# radar.net
KiCad netlist of a schematic drawn in EAGLE
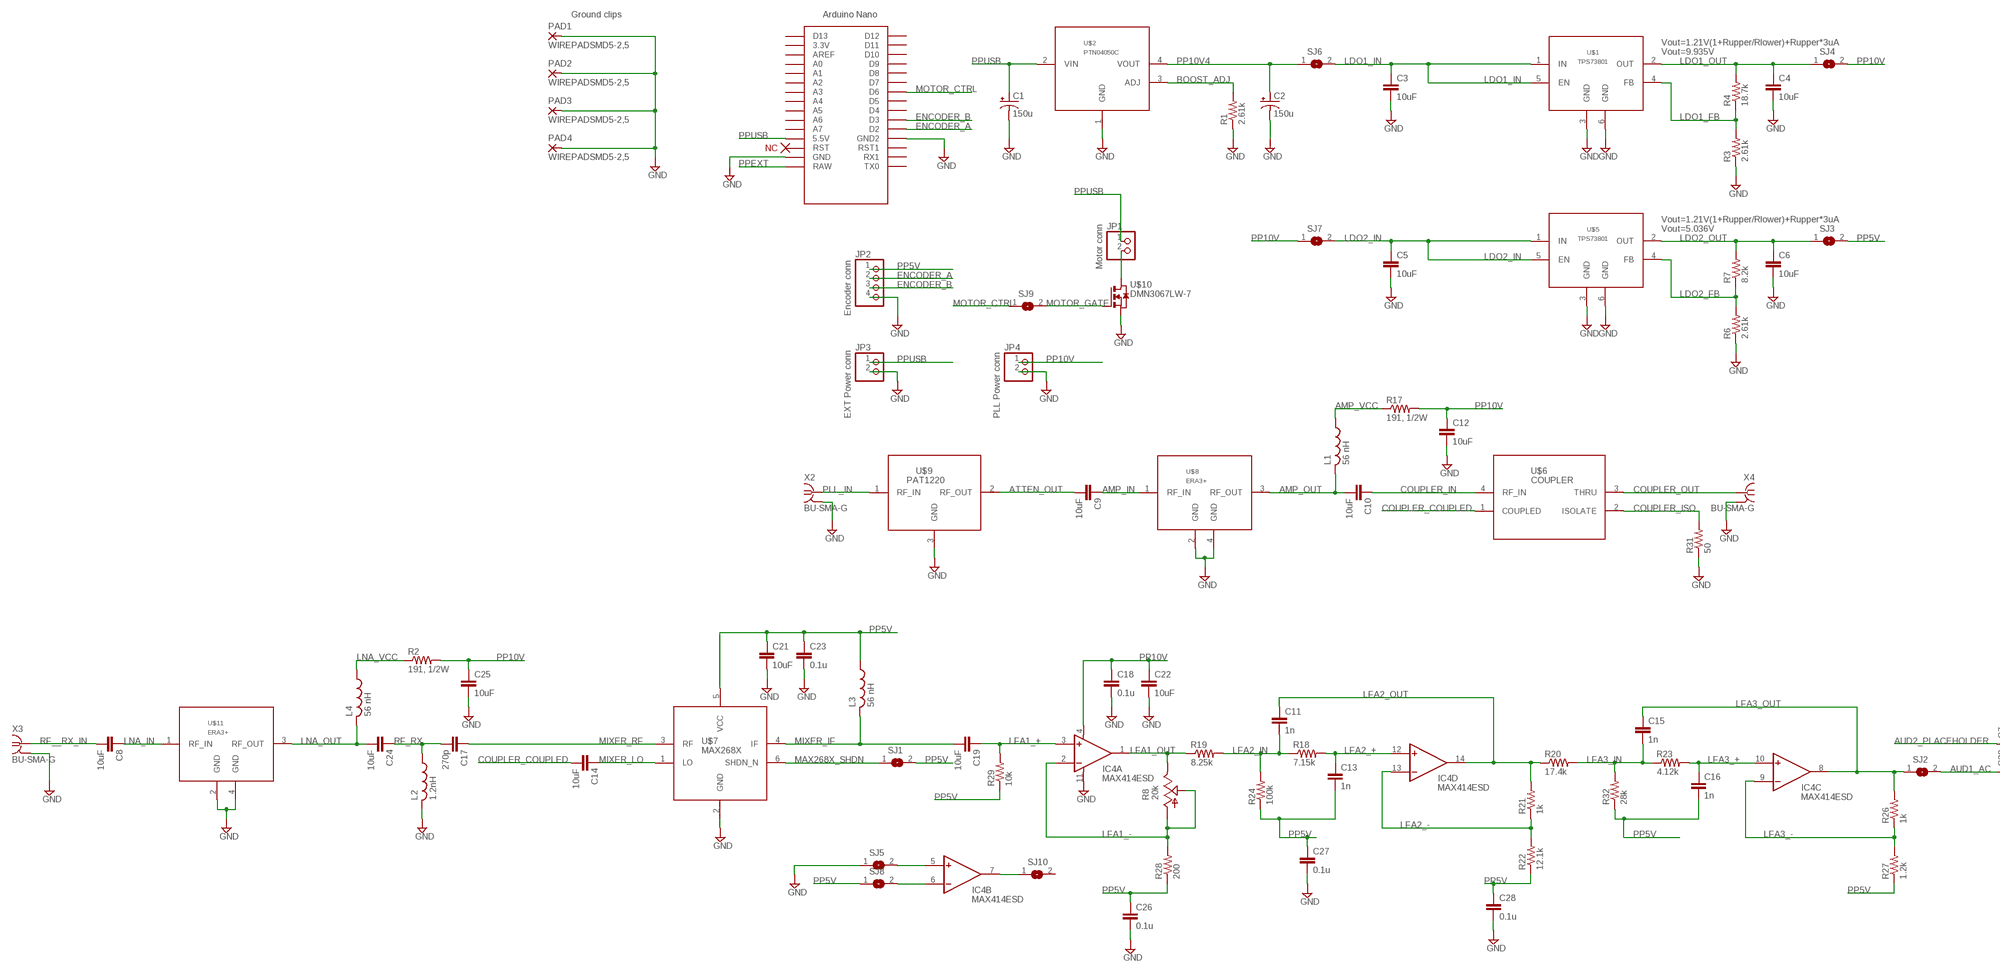
[diagram p0: schematic, sheet 1, part 1 of 2]
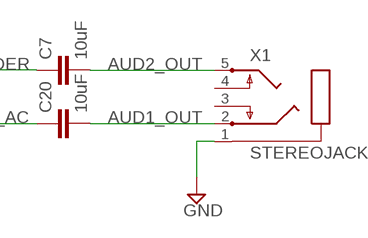
[diagram p1: schematic, sheet 1, part 2 of 2]

(export (version "E")
  (design (tool "Eeschema 10.0.6"))
  (components
    (comp (ref "C1")
      (value "150u")
      (footprint "eagle-import:153CLV-0605")
      (libsource (lib "eagle-import") (part "CPOL-US153CLV-0605"))
    )
    (comp (ref "C2")
      (value "150u")
      (footprint "eagle-import:153CLV-0605")
      (libsource (lib "eagle-import") (part "CPOL-US153CLV-0605"))
    )
    (comp (ref "C3")
      (value "10uF")
      (footprint "eagle-import:C0805K")
      (libsource (lib "eagle-import") (part "C-EUC0805K"))
    )
    (comp (ref "C4")
      (value "10uF")
      (footprint "eagle-import:C0805K")
      (libsource (lib "eagle-import") (part "C-EUC0805K"))
    )
    (comp (ref "C5")
      (value "10uF")
      (footprint "eagle-import:C0805K")
      (libsource (lib "eagle-import") (part "C-EUC0805K"))
    )
    (comp (ref "C6")
      (value "10uF")
      (footprint "eagle-import:C0805K")
      (libsource (lib "eagle-import") (part "C-EUC0805K"))
    )
    (comp (ref "C7")
      (value "10uF")
      (footprint "eagle-import:C0805K")
      (libsource (lib "eagle-import") (part "C-EUC0805K"))
    )
    (comp (ref "C8")
      (value "10uF")
      (footprint "eagle-import:C0805K")
      (libsource (lib "eagle-import") (part "C-EUC0805K"))
    )
    (comp (ref "C9")
      (value "10uF")
      (footprint "eagle-import:C0805K")
      (libsource (lib "eagle-import") (part "C-EUC0805K"))
    )
    (comp (ref "C10")
      (value "10uF")
      (footprint "eagle-import:C0805K")
      (libsource (lib "eagle-import") (part "C-EUC0805K"))
    )
    (comp (ref "C11")
      (value "1n")
      (footprint "eagle-import:C0603")
      (libsource (lib "eagle-import") (part "C-EUC0603"))
    )
    (comp (ref "C12")
      (value "10uF")
      (footprint "eagle-import:C0805K")
      (libsource (lib "eagle-import") (part "C-EUC0805K"))
    )
    (comp (ref "C13")
      (value "1n")
      (footprint "eagle-import:C0603")
      (libsource (lib "eagle-import") (part "C-EUC0603"))
    )
    (comp (ref "C14")
      (value "10uF")
      (footprint "eagle-import:C0805K")
      (libsource (lib "eagle-import") (part "C-EUC0805K"))
    )
    (comp (ref "C15")
      (value "1n")
      (footprint "eagle-import:C0603")
      (libsource (lib "eagle-import") (part "C-EUC0603"))
    )
    (comp (ref "C16")
      (value "1n")
      (footprint "eagle-import:C0603")
      (libsource (lib "eagle-import") (part "C-EUC0603"))
    )
    (comp (ref "C17")
      (value "270p")
      (footprint "eagle-import:C0603K")
      (libsource (lib "eagle-import") (part "C-EUC0603K"))
    )
    (comp (ref "C18")
      (value "0.1u")
      (footprint "eagle-import:C0603")
      (libsource (lib "eagle-import") (part "C-EUC0603"))
    )
    (comp (ref "C19")
      (value "10uF")
      (footprint "eagle-import:C0805K")
      (libsource (lib "eagle-import") (part "C-EUC0805K"))
    )
    (comp (ref "C20")
      (value "10uF")
      (footprint "eagle-import:C0805K")
      (libsource (lib "eagle-import") (part "C-EUC0805K"))
    )
    (comp (ref "C21")
      (value "10uF")
      (footprint "eagle-import:C0805K")
      (libsource (lib "eagle-import") (part "C-EUC0805K"))
    )
    (comp (ref "C22")
      (value "10uF")
      (footprint "eagle-import:C0805K")
      (libsource (lib "eagle-import") (part "C-EUC0805K"))
    )
    (comp (ref "C23")
      (value "0.1u")
      (footprint "eagle-import:C0603")
      (libsource (lib "eagle-import") (part "C-EUC0603"))
    )
    (comp (ref "C24")
      (value "10uF")
      (footprint "eagle-import:C0805K")
      (libsource (lib "eagle-import") (part "C-EUC0805K"))
    )
    (comp (ref "C25")
      (value "10uF")
      (footprint "eagle-import:C0805K")
      (libsource (lib "eagle-import") (part "C-EUC0805K"))
    )
    (comp (ref "C26")
      (value "0.1u")
      (footprint "eagle-import:C0603")
      (libsource (lib "eagle-import") (part "C-EUC0603"))
    )
    (comp (ref "C27")
      (value "0.1u")
      (footprint "eagle-import:C0603")
      (libsource (lib "eagle-import") (part "C-EUC0603"))
    )
    (comp (ref "C28")
      (value "0.1u")
      (footprint "eagle-import:C0603")
      (libsource (lib "eagle-import") (part "C-EUC0603"))
    )
    (comp (ref "IC4")
      (value "MAX414ESD")
      (footprint "eagle-import:SO14")
      (fields (field (name "DIGI") "MAX414ESD+-ND"))
      (libsource (lib "eagle-import") (part "MAX414ESD"))
    )
    (comp (ref "JP1")
      (value "PINHD-1X2")
      (footprint "eagle-import:1X02")
      (libsource (lib "eagle-import") (part "PINHD-1X2"))
    )
    (comp (ref "JP2")
      (value "PINHD-1X4")
      (footprint "eagle-import:1X04")
      (libsource (lib "eagle-import") (part "PINHD-1X4"))
    )
    (comp (ref "JP3")
      (value "PINHD-1X2")
      (footprint "eagle-import:1X02")
      (libsource (lib "eagle-import") (part "PINHD-1X2"))
    )
    (comp (ref "JP4")
      (value "PINHD-1X2")
      (footprint "eagle-import:1X02")
      (libsource (lib "eagle-import") (part "PINHD-1X2"))
    )
    (comp (ref "L1")
      (value "56 nH")
      (footprint "eagle-import:0603")
      (libsource (lib "eagle-import") (part "L0603"))
    )
    (comp (ref "L2")
      (value "1.2nH")
      (footprint "eagle-import:0603")
      (libsource (lib "eagle-import") (part "L0603"))
    )
    (comp (ref "L3")
      (value "56 nH")
      (footprint "eagle-import:0603")
      (libsource (lib "eagle-import") (part "L0603"))
    )
    (comp (ref "L4")
      (value "56 nH")
      (footprint "eagle-import:0603")
      (libsource (lib "eagle-import") (part "L0603"))
    )
    (comp (ref "PAD1")
      (value "WIREPADSMD5-2,5")
      (footprint "eagle-import:5-2,5")
      (libsource (lib "eagle-import") (part "WIREPADSMD5-2,5"))
    )
    (comp (ref "PAD2")
      (value "WIREPADSMD5-2,5")
      (footprint "eagle-import:5-2,5")
      (libsource (lib "eagle-import") (part "WIREPADSMD5-2,5"))
    )
    (comp (ref "PAD3")
      (value "WIREPADSMD5-2,5")
      (footprint "eagle-import:5-2,5")
      (libsource (lib "eagle-import") (part "WIREPADSMD5-2,5"))
    )
    (comp (ref "PAD4")
      (value "WIREPADSMD5-2,5")
      (footprint "eagle-import:5-2,5")
      (libsource (lib "eagle-import") (part "WIREPADSMD5-2,5"))
    )
    (comp (ref "R1")
      (value "2.61k")
      (footprint "eagle-import:R0603")
      (libsource (lib "eagle-import") (part "R-US_R0603"))
    )
    (comp (ref "R2")
      (value "191, 1/2W")
      (footprint "eagle-import:R1210")
      (libsource (lib "eagle-import") (part "R-US_R1210"))
    )
    (comp (ref "R3")
      (value "2.61k")
      (footprint "eagle-import:R0603")
      (libsource (lib "eagle-import") (part "R-US_R0603"))
    )
    (comp (ref "R4")
      (value "18.7k")
      (footprint "eagle-import:R0603")
      (libsource (lib "eagle-import") (part "R-US_R0603"))
    )
    (comp (ref "R6")
      (value "2.61k")
      (footprint "eagle-import:R0603")
      (libsource (lib "eagle-import") (part "R-US_R0603"))
    )
    (comp (ref "R7")
      (value "8.2k")
      (footprint "eagle-import:R0603")
      (libsource (lib "eagle-import") (part "R-US_R0603"))
    )
    (comp (ref "R8")
      (value "20k")
      (footprint "eagle-import:B25P")
      (libsource (lib "eagle-import") (part "TRIM_US-B25P"))
    )
    (comp (ref "R17")
      (value "191, 1/2W")
      (footprint "eagle-import:R1210")
      (libsource (lib "eagle-import") (part "R-US_R1210"))
    )
    (comp (ref "R18")
      (value "7.15k")
      (footprint "eagle-import:R0603")
      (libsource (lib "eagle-import") (part "R-US_R0603"))
    )
    (comp (ref "R19")
      (value "8.25k")
      (footprint "eagle-import:R0603")
      (libsource (lib "eagle-import") (part "R-US_R0603"))
    )
    (comp (ref "R20")
      (value "17.4k")
      (footprint "eagle-import:R0603")
      (libsource (lib "eagle-import") (part "R-US_R0603"))
    )
    (comp (ref "R21")
      (value "1k")
      (footprint "eagle-import:R0603")
      (libsource (lib "eagle-import") (part "R-US_R0603"))
    )
    (comp (ref "R22")
      (value "12.1k")
      (footprint "eagle-import:R0603")
      (libsource (lib "eagle-import") (part "R-US_R0603"))
    )
    (comp (ref "R23")
      (value "4.12k")
      (footprint "eagle-import:R0603")
      (libsource (lib "eagle-import") (part "R-US_R0603"))
    )
    (comp (ref "R24")
      (value "100k")
      (footprint "eagle-import:R0603")
      (libsource (lib "eagle-import") (part "R-US_R0603"))
    )
    (comp (ref "R26")
      (value "1k")
      (footprint "eagle-import:R0603")
      (libsource (lib "eagle-import") (part "R-US_R0603"))
    )
    (comp (ref "R27")
      (value "1.2k")
      (footprint "eagle-import:R0603")
      (libsource (lib "eagle-import") (part "R-US_R0603"))
    )
    (comp (ref "R28")
      (value "200")
      (footprint "eagle-import:R0603")
      (libsource (lib "eagle-import") (part "R-US_R0603"))
    )
    (comp (ref "R29")
      (value "10k")
      (footprint "eagle-import:R0603")
      (libsource (lib "eagle-import") (part "R-US_R0603"))
    )
    (comp (ref "R31")
      (value "50")
      (footprint "eagle-import:R0603")
      (libsource (lib "eagle-import") (part "R-US_R0603"))
    )
    (comp (ref "R32")
      (value "28k")
      (footprint "eagle-import:R0603")
      (libsource (lib "eagle-import") (part "R-US_R0603"))
    )
    (comp (ref "SJ1") (value "SJ") (footprint "eagle-import:SJ") (libsource (lib "eagle-import") (part "SJ")))
    (comp (ref "SJ2") (value "SJ") (footprint "eagle-import:SJ") (libsource (lib "eagle-import") (part "SJ")))
    (comp (ref "SJ3") (value "SJ") (footprint "eagle-import:SJ") (libsource (lib "eagle-import") (part "SJ")))
    (comp (ref "SJ4") (value "SJ") (footprint "eagle-import:SJ") (libsource (lib "eagle-import") (part "SJ")))
    (comp (ref "SJ5") (value "SJ") (footprint "eagle-import:SJ") (libsource (lib "eagle-import") (part "SJ")))
    (comp (ref "SJ6") (value "SJ") (footprint "eagle-import:SJ") (libsource (lib "eagle-import") (part "SJ")))
    (comp (ref "SJ7") (value "SJ") (footprint "eagle-import:SJ") (libsource (lib "eagle-import") (part "SJ")))
    (comp (ref "SJ8") (value "SJ") (footprint "eagle-import:SJ") (libsource (lib "eagle-import") (part "SJ")))
    (comp (ref "SJ9") (value "SJ") (footprint "eagle-import:SJ") (libsource (lib "eagle-import") (part "SJ")))
    (comp (ref "SJ10")
      (value "SJ")
      (footprint "eagle-import:SJ")
      (libsource (lib "eagle-import") (part "SJ"))
    )
    (comp (ref "U$1")
      (value "TPS73801")
      (footprint "eagle-import:SOT223-6")
      (libsource (lib "eagle-import") (part "TPS73801"))
    )
    (comp (ref "U$2")
      (value "PTN04050C")
      (footprint "eagle-import:PTN04050C")
      (libsource (lib "eagle-import") (part "PTN04050C"))
    )
    (comp (ref "U$3")
      (value "NANO")
      (footprint "eagle-import:NANO")
      (libsource (lib "eagle-import") (part "NANO"))
    )
    (comp (ref "U$5")
      (value "TPS73801")
      (footprint "eagle-import:SOT223-6")
      (libsource (lib "eagle-import") (part "TPS73801"))
    )
    (comp (ref "U$6")
      (value "COUPLER")
      (footprint "eagle-import:COUPLER")
      (libsource (lib "eagle-import") (part "COUPLER"))
    )
    (comp (ref "U$7")
      (value "MAX268X")
      (footprint "eagle-import:SOT23-6")
      (libsource (lib "eagle-import") (part "MAX268X"))
    )
    (comp (ref "U$8")
      (value "ERA3+")
      (footprint "eagle-import:ERA3+")
      (libsource (lib "eagle-import") (part "ERA3+"))
    )
    (comp (ref "U$9")
      (value "PAT1220")
      (footprint "eagle-import:PAT1220")
      (libsource (lib "eagle-import") (part "PAT1220"))
    )
    (comp (ref "U$10")
      (value "DMN3067LW-7")
      (footprint "eagle-import:SOT323")
      (libsource (lib "eagle-import") (part "DMN3067LW-7"))
    )
    (comp (ref "U$11")
      (value "ERA3+")
      (footprint "eagle-import:ERA3+")
      (libsource (lib "eagle-import") (part "ERA3+"))
    )
    (comp (ref "X1")
      (value "STEREOJACK")
      (footprint "eagle-import:STX3100")
      (libsource (lib "eagle-import") (part "STEREOJACK"))
    )
    (comp (ref "X2")
      (value "BU-SMA-G")
      (footprint "eagle-import:BU-SMA-G")
      (libsource (lib "eagle-import") (part "BU-SMA-G"))
    )
    (comp (ref "X3")
      (value "BU-SMA-G")
      (footprint "eagle-import:BU-SMA-G")
      (libsource (lib "eagle-import") (part "BU-SMA-G"))
    )
    (comp (ref "X4")
      (value "BU-SMA-G")
      (footprint "eagle-import:BU-SMA-G")
      (libsource (lib "eagle-import") (part "BU-SMA-G"))
    )
  )
  (nets
    (net (code "1") (name "/AMP_IN") (class "Default")
      (node (ref "C9") (pin "1") (pinfunction "1_1") (pintype "passive"))
      (node (ref "U$8") (pin "1") (pinfunction "RF_IN_1") (pintype "bidirectional"))
    )
    (net (code "2") (name "/AMP_OUT") (class "Default")
      (node (ref "C10") (pin "2") (pinfunction "2_2") (pintype "passive"))
      (node (ref "L1") (pin "2") (pinfunction "2_2") (pintype "passive"))
      (node (ref "U$8") (pin "3") (pinfunction "RF_OUT_3") (pintype "bidirectional"))
    )
    (net (code "3") (name "/AMP_VCC") (class "Default")
      (node (ref "L1") (pin "1") (pinfunction "1_1") (pintype "passive"))
      (node (ref "R17") (pin "1") (pinfunction "1_1") (pintype "passive"))
    )
    (net (code "4") (name "/ATTEN_OUT") (class "Default")
      (node (ref "C9") (pin "2") (pinfunction "2_2") (pintype "passive"))
      (node (ref "U$9") (pin "2") (pinfunction "RF_OUT_2") (pintype "bidirectional"))
    )
    (net (code "5") (name "/AUD1_AC") (class "Default")
      (node (ref "C20") (pin "1") (pinfunction "1_1") (pintype "passive"))
      (node (ref "SJ2") (pin "2") (pinfunction "2_2") (pintype "passive"))
    )
    (net (code "6") (name "/AUD1_OUT") (class "Default")
      (node (ref "C20") (pin "2") (pinfunction "2_2") (pintype "passive"))
      (node (ref "X1") (pin "2") (pinfunction "2_2") (pintype "passive"))
    )
    (net (code "7") (name "/AUD2_OUT") (class "Default")
      (node (ref "C7") (pin "2") (pinfunction "2_2") (pintype "passive"))
      (node (ref "X1") (pin "5") (pinfunction "5_5") (pintype "passive"))
    )
    (net (code "8") (name "/AUD2_PLACEHOLDER") (class "Default")
      (node (ref "C7") (pin "1") (pinfunction "1_1") (pintype "passive"))
    )
    (net (code "9") (name "/BOOST_ADJ") (class "Default")
      (node (ref "R1") (pin "2") (pinfunction "2_2") (pintype "passive"))
      (node (ref "U$2") (pin "3") (pinfunction "ADJ_3") (pintype "bidirectional"))
    )
    (net (code "10") (name "/COUPLER_COUPLED") (class "Default")
      (node (ref "C14") (pin "2") (pinfunction "2_2") (pintype "passive"))
      (node (ref "U$6") (pin "1") (pinfunction "COUPLED_1") (pintype "bidirectional"))
    )
    (net (code "11") (name "/COUPLER_IN") (class "Default")
      (node (ref "C10") (pin "1") (pinfunction "1_1") (pintype "passive"))
      (node (ref "U$6") (pin "4") (pinfunction "RF_IN_4") (pintype "bidirectional"))
    )
    (net (code "12") (name "/COUPLER_ISO") (class "Default")
      (node (ref "R31") (pin "2") (pinfunction "2_2") (pintype "passive"))
      (node (ref "U$6") (pin "2") (pinfunction "ISOLATE_2") (pintype "bidirectional"))
    )
    (net (code "13") (name "/COUPLER_OUT") (class "Default")
      (node (ref "U$6") (pin "3") (pinfunction "THRU_3") (pintype "bidirectional"))
      (node (ref "X4") (pin "1") (pinfunction "1_1") (pintype "passive"))
    )
    (net (code "14") (name "/ENCODER_A") (class "Default")
      (node (ref "JP2") (pin "2") (pinfunction "2_2") (pintype "passive"))
      (node (ref "U$3") (pin "D2") (pinfunction "D2_D2") (pintype "bidirectional"))
    )
    (net (code "15") (name "/ENCODER_B") (class "Default")
      (node (ref "JP2") (pin "3") (pinfunction "3_3") (pintype "passive"))
      (node (ref "U$3") (pin "D3") (pinfunction "D3_D3") (pintype "bidirectional"))
    )
    (net (code "16") (name "/LDO1_FB") (class "Default")
      (node (ref "R3") (pin "2") (pinfunction "2_2") (pintype "passive"))
      (node (ref "R4") (pin "1") (pinfunction "1_1") (pintype "passive"))
      (node (ref "U$1") (pin "4") (pinfunction "FB_4") (pintype "bidirectional"))
    )
    (net (code "17") (name "/LDO1_IN") (class "Default")
      (node (ref "C3") (pin "1") (pinfunction "1_1") (pintype "passive"))
      (node (ref "SJ6") (pin "2") (pinfunction "2_2") (pintype "passive"))
      (node (ref "U$1") (pin "1") (pinfunction "IN_1") (pintype "bidirectional"))
      (node (ref "U$1") (pin "5") (pinfunction "EN_5") (pintype "bidirectional"))
    )
    (net (code "18") (name "/LDO1_OUT") (class "Default")
      (node (ref "C4") (pin "1") (pinfunction "1_1") (pintype "passive"))
      (node (ref "R4") (pin "2") (pinfunction "2_2") (pintype "passive"))
      (node (ref "SJ4") (pin "1") (pinfunction "1_1") (pintype "passive"))
      (node (ref "U$1") (pin "2") (pinfunction "OUT_2") (pintype "bidirectional"))
    )
    (net (code "19") (name "/LDO2_FB") (class "Default")
      (node (ref "R6") (pin "2") (pinfunction "2_2") (pintype "passive"))
      (node (ref "R7") (pin "1") (pinfunction "1_1") (pintype "passive"))
      (node (ref "U$5") (pin "4") (pinfunction "FB_4") (pintype "bidirectional"))
    )
    (net (code "20") (name "/LDO2_IN") (class "Default")
      (node (ref "C5") (pin "1") (pinfunction "1_1") (pintype "passive"))
      (node (ref "SJ7") (pin "2") (pinfunction "2_2") (pintype "passive"))
      (node (ref "U$5") (pin "1") (pinfunction "IN_1") (pintype "bidirectional"))
      (node (ref "U$5") (pin "5") (pinfunction "EN_5") (pintype "bidirectional"))
    )
    (net (code "21") (name "/LDO2_OUT") (class "Default")
      (node (ref "C6") (pin "1") (pinfunction "1_1") (pintype "passive"))
      (node (ref "R7") (pin "2") (pinfunction "2_2") (pintype "passive"))
      (node (ref "SJ3") (pin "1") (pinfunction "1_1") (pintype "passive"))
      (node (ref "U$5") (pin "2") (pinfunction "OUT_2") (pintype "bidirectional"))
    )
    (net (code "22") (name "/LFA1_+") (class "Default")
      (node (ref "C19") (pin "1") (pinfunction "1_1") (pintype "passive"))
      (node (ref "IC4") (pin "3") (pinfunction "+IN_3") (pintype "input"))
      (node (ref "R29") (pin "2") (pinfunction "2_2") (pintype "passive"))
    )
    (net (code "23") (name "/LFA1_-") (class "Default")
      (node (ref "IC4") (pin "2") (pinfunction "-IN_2") (pintype "input"))
      (node (ref "R28") (pin "2") (pinfunction "2_2") (pintype "passive"))
      (node (ref "R8") (pin "A") (pinfunction "A_A") (pintype "passive"))
      (node (ref "R8") (pin "S") (pinfunction "S_S") (pintype "passive"))
    )
    (net (code "24") (name "/LFA1_OUT") (class "Default")
      (node (ref "IC4") (pin "1") (pinfunction "OUT_1") (pintype "output"))
      (node (ref "R19") (pin "1") (pinfunction "1_1") (pintype "passive"))
      (node (ref "R8") (pin "E") (pinfunction "E_E") (pintype "passive"))
    )
    (net (code "25") (name "/LFA2_+") (class "Default")
      (node (ref "C13") (pin "1") (pinfunction "1_1") (pintype "passive"))
      (node (ref "IC4") (pin "12") (pinfunction "+IN_12") (pintype "input"))
      (node (ref "R18") (pin "2") (pinfunction "2_2") (pintype "passive"))
    )
    (net (code "26") (name "/LFA2_-") (class "Default")
      (node (ref "IC4") (pin "13") (pinfunction "-IN_13") (pintype "input"))
      (node (ref "R21") (pin "1") (pinfunction "1_1") (pintype "passive"))
      (node (ref "R22") (pin "2") (pinfunction "2_2") (pintype "passive"))
    )
    (net (code "27") (name "/LFA2_IN") (class "Default")
      (node (ref "C11") (pin "2") (pinfunction "2_2") (pintype "passive"))
      (node (ref "R18") (pin "1") (pinfunction "1_1") (pintype "passive"))
      (node (ref "R19") (pin "2") (pinfunction "2_2") (pintype "passive"))
      (node (ref "R24") (pin "2") (pinfunction "2_2") (pintype "passive"))
    )
    (net (code "28") (name "/LFA2_OUT") (class "Default")
      (node (ref "C11") (pin "1") (pinfunction "1_1") (pintype "passive"))
      (node (ref "IC4") (pin "14") (pinfunction "OUT_14") (pintype "output"))
      (node (ref "R20") (pin "1") (pinfunction "1_1") (pintype "passive"))
      (node (ref "R21") (pin "2") (pinfunction "2_2") (pintype "passive"))
    )
    (net (code "29") (name "/LFA3_+") (class "Default")
      (node (ref "C16") (pin "1") (pinfunction "1_1") (pintype "passive"))
      (node (ref "IC4") (pin "10") (pinfunction "+IN_10") (pintype "input"))
      (node (ref "R23") (pin "2") (pinfunction "2_2") (pintype "passive"))
    )
    (net (code "30") (name "/LFA3_-") (class "Default")
      (node (ref "IC4") (pin "9") (pinfunction "-IN_9") (pintype "input"))
      (node (ref "R26") (pin "1") (pinfunction "1_1") (pintype "passive"))
      (node (ref "R27") (pin "2") (pinfunction "2_2") (pintype "passive"))
    )
    (net (code "31") (name "/LFA3_IN") (class "Default")
      (node (ref "C15") (pin "2") (pinfunction "2_2") (pintype "passive"))
      (node (ref "R20") (pin "2") (pinfunction "2_2") (pintype "passive"))
      (node (ref "R23") (pin "1") (pinfunction "1_1") (pintype "passive"))
      (node (ref "R32") (pin "2") (pinfunction "2_2") (pintype "passive"))
    )
    (net (code "32") (name "/LFA3_OUT") (class "Default")
      (node (ref "C15") (pin "1") (pinfunction "1_1") (pintype "passive"))
      (node (ref "IC4") (pin "8") (pinfunction "OUT_8") (pintype "output"))
      (node (ref "R26") (pin "2") (pinfunction "2_2") (pintype "passive"))
      (node (ref "SJ2") (pin "1") (pinfunction "1_1") (pintype "passive"))
    )
    (net (code "33") (name "/LNA_IN") (class "Default")
      (node (ref "C8") (pin "1") (pinfunction "1_1") (pintype "passive"))
      (node (ref "U$11") (pin "1") (pinfunction "RF_IN_1") (pintype "bidirectional"))
    )
    (net (code "34") (name "/LNA_OUT") (class "Default")
      (node (ref "C24") (pin "2") (pinfunction "2_2") (pintype "passive"))
      (node (ref "L4") (pin "2") (pinfunction "2_2") (pintype "passive"))
      (node (ref "U$11") (pin "3") (pinfunction "RF_OUT_3") (pintype "bidirectional"))
    )
    (net (code "35") (name "/LNA_VCC") (class "Default")
      (node (ref "L4") (pin "1") (pinfunction "1_1") (pintype "passive"))
      (node (ref "R2") (pin "1") (pinfunction "1_1") (pintype "passive"))
    )
    (net (code "36") (name "/MAX268X_SHDN") (class "Default")
      (node (ref "SJ1") (pin "1") (pinfunction "1_1") (pintype "passive"))
      (node (ref "U$7") (pin "6") (pinfunction "SHDN_N_6") (pintype "bidirectional"))
    )
    (net (code "37") (name "/MIXER_IF") (class "Default")
      (node (ref "C19") (pin "2") (pinfunction "2_2") (pintype "passive"))
      (node (ref "L3") (pin "2") (pinfunction "2_2") (pintype "passive"))
      (node (ref "U$7") (pin "4") (pinfunction "IF_4") (pintype "bidirectional"))
    )
    (net (code "38") (name "/MIXER_LO") (class "Default")
      (node (ref "C14") (pin "1") (pinfunction "1_1") (pintype "passive"))
      (node (ref "U$7") (pin "1") (pinfunction "LO_1") (pintype "bidirectional"))
    )
    (net (code "39") (name "/MIXER_RF") (class "Default")
      (node (ref "C17") (pin "1") (pinfunction "1_1") (pintype "passive"))
      (node (ref "U$7") (pin "3") (pinfunction "RF_3") (pintype "bidirectional"))
    )
    (net (code "40") (name "/MOTOR_CTRL") (class "Default")
      (node (ref "SJ9") (pin "1") (pinfunction "1_1") (pintype "passive"))
      (node (ref "U$3") (pin "D6") (pinfunction "D6_D6") (pintype "bidirectional"))
    )
    (net (code "41") (name "/MOTOR_GATE") (class "Default")
      (node (ref "SJ9") (pin "2") (pinfunction "2_2") (pintype "passive"))
      (node (ref "U$10") (pin "1") (pinfunction "G_1") (pintype "passive"))
    )
    (net (code "42") (name "/PLL_IN") (class "Default")
      (node (ref "U$9") (pin "1") (pinfunction "RF_IN_1") (pintype "bidirectional"))
      (node (ref "X2") (pin "1") (pinfunction "1_1") (pintype "passive"))
    )
    (net (code "43") (name "/PP5V") (class "Default")
      (node (ref "C13") (pin "2") (pinfunction "2_2") (pintype "passive"))
      (node (ref "C16") (pin "2") (pinfunction "2_2") (pintype "passive"))
      (node (ref "C21") (pin "1") (pinfunction "1_1") (pintype "passive"))
      (node (ref "C23") (pin "1") (pinfunction "1_1") (pintype "passive"))
      (node (ref "C26") (pin "1") (pinfunction "1_1") (pintype "passive"))
      (node (ref "C27") (pin "1") (pinfunction "1_1") (pintype "passive"))
      (node (ref "C28") (pin "1") (pinfunction "1_1") (pintype "passive"))
      (node (ref "JP2") (pin "1") (pinfunction "1_1") (pintype "passive"))
      (node (ref "L3") (pin "1") (pinfunction "1_1") (pintype "passive"))
      (node (ref "R22") (pin "1") (pinfunction "1_1") (pintype "passive"))
      (node (ref "R24") (pin "1") (pinfunction "1_1") (pintype "passive"))
      (node (ref "R27") (pin "1") (pinfunction "1_1") (pintype "passive"))
      (node (ref "R28") (pin "1") (pinfunction "1_1") (pintype "passive"))
      (node (ref "R29") (pin "1") (pinfunction "1_1") (pintype "passive"))
      (node (ref "R32") (pin "1") (pinfunction "1_1") (pintype "passive"))
      (node (ref "SJ1") (pin "2") (pinfunction "2_2") (pintype "passive"))
      (node (ref "SJ3") (pin "2") (pinfunction "2_2") (pintype "passive"))
      (node (ref "SJ8") (pin "1") (pinfunction "1_1") (pintype "passive"))
      (node (ref "U$7") (pin "5") (pinfunction "VCC_5") (pintype "bidirectional"))
    )
    (net (code "44") (name "/PP10V") (class "Default")
      (node (ref "C12") (pin "1") (pinfunction "1_1") (pintype "passive"))
      (node (ref "C18") (pin "1") (pinfunction "1_1") (pintype "passive"))
      (node (ref "C22") (pin "1") (pinfunction "1_1") (pintype "passive"))
      (node (ref "C25") (pin "1") (pinfunction "1_1") (pintype "passive"))
      (node (ref "IC4") (pin "4") (pinfunction "V+_4") (pintype "power_in"))
      (node (ref "JP4") (pin "1") (pinfunction "1_1") (pintype "passive"))
      (node (ref "R17") (pin "2") (pinfunction "2_2") (pintype "passive"))
      (node (ref "R2") (pin "2") (pinfunction "2_2") (pintype "passive"))
      (node (ref "SJ4") (pin "2") (pinfunction "2_2") (pintype "passive"))
      (node (ref "SJ7") (pin "1") (pinfunction "1_1") (pintype "passive"))
    )
    (net (code "45") (name "/PP10V4") (class "Default")
      (node (ref "C2") (pin "+") (pinfunction "+_+") (pintype "passive"))
      (node (ref "SJ6") (pin "1") (pinfunction "1_1") (pintype "passive"))
      (node (ref "U$2") (pin "4") (pinfunction "VOUT_4") (pintype "bidirectional"))
    )
    (net (code "46") (name "/PPEXT") (class "Default")
      (node (ref "U$3") (pin "RAW") (pinfunction "RAW_RAW") (pintype "bidirectional"))
    )
    (net (code "47") (name "/PPUSB") (class "Default")
      (node (ref "C1") (pin "+") (pinfunction "+_+") (pintype "passive"))
      (node (ref "JP1") (pin "1") (pinfunction "1_1") (pintype "passive"))
      (node (ref "JP3") (pin "1") (pinfunction "1_1") (pintype "passive"))
      (node (ref "U$2") (pin "2") (pinfunction "VIN_2") (pintype "bidirectional"))
      (node (ref "U$3") (pin "5V") (pinfunction "5.5V_5V") (pintype "bidirectional"))
    )
    (net (code "48") (name "/RF_RX") (class "Default")
      (node (ref "C17") (pin "2") (pinfunction "2_2") (pintype "passive"))
      (node (ref "C24") (pin "1") (pinfunction "1_1") (pintype "passive"))
      (node (ref "L2") (pin "1") (pinfunction "1_1") (pintype "passive"))
    )
    (net (code "49") (name "/RF__RX_IN") (class "Default")
      (node (ref "C8") (pin "2") (pinfunction "2_2") (pintype "passive"))
      (node (ref "X3") (pin "1") (pinfunction "1_1") (pintype "passive"))
    )
    (net (code "50") (name "GND") (class "Default")
      (node (ref "C1") (pin "-") (pinfunction "-_-") (pintype "passive"))
      (node (ref "C12") (pin "2") (pinfunction "2_2") (pintype "passive"))
      (node (ref "C18") (pin "2") (pinfunction "2_2") (pintype "passive"))
      (node (ref "C2") (pin "-") (pinfunction "-_-") (pintype "passive"))
      (node (ref "C21") (pin "2") (pinfunction "2_2") (pintype "passive"))
      (node (ref "C22") (pin "2") (pinfunction "2_2") (pintype "passive"))
      (node (ref "C23") (pin "2") (pinfunction "2_2") (pintype "passive"))
      (node (ref "C25") (pin "2") (pinfunction "2_2") (pintype "passive"))
      (node (ref "C26") (pin "2") (pinfunction "2_2") (pintype "passive"))
      (node (ref "C27") (pin "2") (pinfunction "2_2") (pintype "passive"))
      (node (ref "C28") (pin "2") (pinfunction "2_2") (pintype "passive"))
      (node (ref "C3") (pin "2") (pinfunction "2_2") (pintype "passive"))
      (node (ref "C4") (pin "2") (pinfunction "2_2") (pintype "passive"))
      (node (ref "C5") (pin "2") (pinfunction "2_2") (pintype "passive"))
      (node (ref "C6") (pin "2") (pinfunction "2_2") (pintype "passive"))
      (node (ref "IC4") (pin "11") (pinfunction "V-_11") (pintype "power_in"))
      (node (ref "JP2") (pin "4") (pinfunction "4_4") (pintype "passive"))
      (node (ref "JP3") (pin "2") (pinfunction "2_2") (pintype "passive"))
      (node (ref "JP4") (pin "2") (pinfunction "2_2") (pintype "passive"))
      (node (ref "L2") (pin "2") (pinfunction "2_2") (pintype "passive"))
      (node (ref "PAD1") (pin "1") (pinfunction "P_1") (pintype "passive"))
      (node (ref "PAD2") (pin "1") (pinfunction "P_1") (pintype "passive"))
      (node (ref "PAD3") (pin "1") (pinfunction "P_1") (pintype "passive"))
      (node (ref "PAD4") (pin "1") (pinfunction "P_1") (pintype "passive"))
      (node (ref "R1") (pin "1") (pinfunction "1_1") (pintype "passive"))
      (node (ref "R3") (pin "1") (pinfunction "1_1") (pintype "passive"))
      (node (ref "R31") (pin "1") (pinfunction "1_1") (pintype "passive"))
      (node (ref "R6") (pin "1") (pinfunction "1_1") (pintype "passive"))
      (node (ref "SJ5") (pin "1") (pinfunction "1_1") (pintype "passive"))
      (node (ref "U$1") (pin "3") (pinfunction "GND_3") (pintype "bidirectional"))
      (node (ref "U$1") (pin "6") (pinfunction "GND_6") (pintype "bidirectional"))
      (node (ref "U$10") (pin "2") (pinfunction "S_2") (pintype "passive"))
      (node (ref "U$11") (pin "2") (pinfunction "GND_2") (pintype "bidirectional"))
      (node (ref "U$11") (pin "4") (pinfunction "GND_4") (pintype "bidirectional"))
      (node (ref "U$2") (pin "1") (pinfunction "GND_1") (pintype "bidirectional"))
      (node (ref "U$3") (pin "GND") (pinfunction "GND_GND") (pintype "bidirectional"))
      (node (ref "U$3") (pin "GND1") (pinfunction "GND2_GND1") (pintype "bidirectional"))
      (node (ref "U$5") (pin "3") (pinfunction "GND_3") (pintype "bidirectional"))
      (node (ref "U$5") (pin "6") (pinfunction "GND_6") (pintype "bidirectional"))
      (node (ref "U$7") (pin "2") (pinfunction "GND_2") (pintype "bidirectional"))
      (node (ref "U$8") (pin "2") (pinfunction "GND_2") (pintype "bidirectional"))
      (node (ref "U$8") (pin "4") (pinfunction "GND_4") (pintype "bidirectional"))
      (node (ref "U$9") (pin "3") (pinfunction "GND_3") (pintype "bidirectional"))
      (node (ref "X1") (pin "1") (pinfunction "1_1") (pintype "passive"))
      (node (ref "X2") (pin "2") (pinfunction "2_2") (pintype "passive"))
      (node (ref "X2") (pin "3") (pinfunction "2_3") (pintype "passive"))
      (node (ref "X2") (pin "4") (pinfunction "2_4") (pintype "passive"))
      (node (ref "X2") (pin "5") (pinfunction "2_5") (pintype "passive"))
      (node (ref "X3") (pin "2") (pinfunction "2_2") (pintype "passive"))
      (node (ref "X3") (pin "3") (pinfunction "2_3") (pintype "passive"))
      (node (ref "X3") (pin "4") (pinfunction "2_4") (pintype "passive"))
      (node (ref "X3") (pin "5") (pinfunction "2_5") (pintype "passive"))
      (node (ref "X4") (pin "2") (pinfunction "2_2") (pintype "passive"))
      (node (ref "X4") (pin "3") (pinfunction "2_3") (pintype "passive"))
      (node (ref "X4") (pin "4") (pinfunction "2_4") (pintype "passive"))
      (node (ref "X4") (pin "5") (pinfunction "2_5") (pintype "passive"))
    )
    (net (code "51") (name "Net-(IC4B-+IN)") (class "Default")
      (node (ref "IC4") (pin "5") (pinfunction "+IN_5") (pintype "input"))
      (node (ref "SJ5") (pin "2") (pinfunction "2_2") (pintype "passive"))
    )
    (net (code "52") (name "Net-(IC4B--IN)") (class "Default")
      (node (ref "IC4") (pin "6") (pinfunction "-IN_6") (pintype "input"))
      (node (ref "SJ8") (pin "2") (pinfunction "2_2") (pintype "passive"))
    )
    (net (code "53") (name "Net-(IC4B-OUT)") (class "Default")
      (node (ref "IC4") (pin "7") (pinfunction "OUT_7") (pintype "output"))
      (node (ref "SJ10") (pin "1") (pinfunction "1_1") (pintype "passive"))
    )
    (net (code "54") (name "Net-(U$10-D)") (class "Default")
      (node (ref "JP1") (pin "2") (pinfunction "2_2") (pintype "passive"))
      (node (ref "U$10") (pin "3") (pinfunction "D_3") (pintype "passive"))
    )
    (net (code "55") (name "unconnected-(SJ10-Pad2)") (class "Default")
      (node (ref "SJ10") (pin "2") (pinfunction "2_2") (pintype "passive"))
    )
    (net (code "56") (name "unconnected-(U$3-Pad3.3V)") (class "Default")
      (node (ref "U$3") (pin "3.3V") (pinfunction "3.3V_3.3V") (pintype "bidirectional"))
    )
    (net (code "57") (name "unconnected-(U$3-PadA0)") (class "Default")
      (node (ref "U$3") (pin "A0") (pinfunction "A0_A0") (pintype "bidirectional"))
    )
    (net (code "58") (name "unconnected-(U$3-PadA1)") (class "Default")
      (node (ref "U$3") (pin "A1") (pinfunction "A1_A1") (pintype "bidirectional"))
    )
    (net (code "59") (name "unconnected-(U$3-PadA2)") (class "Default")
      (node (ref "U$3") (pin "A2") (pinfunction "A2_A2") (pintype "bidirectional"))
    )
    (net (code "60") (name "unconnected-(U$3-PadA3)") (class "Default")
      (node (ref "U$3") (pin "A3") (pinfunction "A3_A3") (pintype "bidirectional"))
    )
    (net (code "61") (name "unconnected-(U$3-PadA4)") (class "Default")
      (node (ref "U$3") (pin "A4") (pinfunction "A4_A4") (pintype "bidirectional"))
    )
    (net (code "62") (name "unconnected-(U$3-PadA5)") (class "Default")
      (node (ref "U$3") (pin "A5") (pinfunction "A5_A5") (pintype "bidirectional"))
    )
    (net (code "63") (name "unconnected-(U$3-PadA6)") (class "Default")
      (node (ref "U$3") (pin "A6") (pinfunction "A6_A6") (pintype "bidirectional"))
    )
    (net (code "64") (name "unconnected-(U$3-PadA7)") (class "Default")
      (node (ref "U$3") (pin "A7") (pinfunction "A7_A7") (pintype "bidirectional"))
    )
    (net (code "65") (name "unconnected-(U$3-PadAREF)") (class "Default")
      (node (ref "U$3") (pin "AREF") (pinfunction "AREF_AREF") (pintype "bidirectional"))
    )
    (net (code "66") (name "unconnected-(U$3-PadD4)") (class "Default")
      (node (ref "U$3") (pin "D4") (pinfunction "D4_D4") (pintype "bidirectional"))
    )
    (net (code "67") (name "unconnected-(U$3-PadD5)") (class "Default")
      (node (ref "U$3") (pin "D5") (pinfunction "D5_D5") (pintype "bidirectional"))
    )
    (net (code "68") (name "unconnected-(U$3-PadD7)") (class "Default")
      (node (ref "U$3") (pin "D7") (pinfunction "D7_D7") (pintype "bidirectional"))
    )
    (net (code "69") (name "unconnected-(U$3-PadD8)") (class "Default")
      (node (ref "U$3") (pin "D8") (pinfunction "D8_D8") (pintype "bidirectional"))
    )
    (net (code "70") (name "unconnected-(U$3-PadD9)") (class "Default")
      (node (ref "U$3") (pin "D9") (pinfunction "D9_D9") (pintype "bidirectional"))
    )
    (net (code "71") (name "unconnected-(U$3-PadD10)") (class "Default")
      (node (ref "U$3") (pin "D10") (pinfunction "D10_D10") (pintype "bidirectional"))
    )
    (net (code "72") (name "unconnected-(U$3-PadD11)") (class "Default")
      (node (ref "U$3") (pin "D11") (pinfunction "D11_D11") (pintype "bidirectional"))
    )
    (net (code "73") (name "unconnected-(U$3-PadD12)") (class "Default")
      (node (ref "U$3") (pin "D12") (pinfunction "D12_D12") (pintype "bidirectional"))
    )
    (net (code "74") (name "unconnected-(U$3-PadD13)") (class "Default")
      (node (ref "U$3") (pin "D13") (pinfunction "D13_D13") (pintype "bidirectional"))
    )
    (net (code "75") (name "unconnected-(U$3-PadICSP1)") (class "Default")
      (node (ref "U$3") (pin "ICSP1") (pinfunction "ICSP1_ICSP1") (pintype "bidirectional"))
    )
    (net (code "76") (name "unconnected-(U$3-PadICSP2)") (class "Default")
      (node (ref "U$3") (pin "ICSP2") (pinfunction "ICSP2_ICSP2") (pintype "bidirectional"))
    )
    (net (code "77") (name "unconnected-(U$3-PadICSP3)") (class "Default")
      (node (ref "U$3") (pin "ICSP3") (pinfunction "ICSP3_ICSP3") (pintype "bidirectional"))
    )
    (net (code "78") (name "unconnected-(U$3-PadICSP4)") (class "Default")
      (node (ref "U$3") (pin "ICSP4") (pinfunction "ICSP4_ICSP4") (pintype "bidirectional"))
    )
    (net (code "79") (name "unconnected-(U$3-PadICSP5)") (class "Default")
      (node (ref "U$3") (pin "ICSP5") (pinfunction "ICSP5_ICSP5") (pintype "bidirectional"))
    )
    (net (code "80") (name "unconnected-(U$3-PadICSP6)") (class "Default")
      (node (ref "U$3") (pin "ICSP6") (pinfunction "ICSP6_ICSP6") (pintype "bidirectional"))
    )
    (net (code "81") (name "unconnected-(U$3-PadRST)") (class "Default")
      (node (ref "U$3") (pin "RST") (pinfunction "RST_RST") (pintype "bidirectional"))
    )
    (net (code "82") (name "unconnected-(U$3-PadRST1)") (class "Default")
      (node (ref "U$3") (pin "RST1") (pinfunction "RST1_RST1") (pintype "bidirectional"))
    )
    (net (code "83") (name "unconnected-(U$3-PadRX1)") (class "Default")
      (node (ref "U$3") (pin "RX1") (pinfunction "RX1_RX1") (pintype "bidirectional"))
    )
    (net (code "84") (name "unconnected-(U$3-PadTX0)") (class "Default")
      (node (ref "U$3") (pin "TX0") (pinfunction "TX0_TX0") (pintype "bidirectional"))
    )
    (net (code "85") (name "unconnected-(X1-Pad3)") (class "Default")
      (node (ref "X1") (pin "3") (pinfunction "3_3") (pintype "passive"))
    )
    (net (code "86") (name "unconnected-(X1-Pad4)") (class "Default")
      (node (ref "X1") (pin "4") (pinfunction "4_4") (pintype "passive"))
    )
  )
)
